# LT3045_1A_mini_module.net
KiCad netlist of a schematic drawn in EAGLE
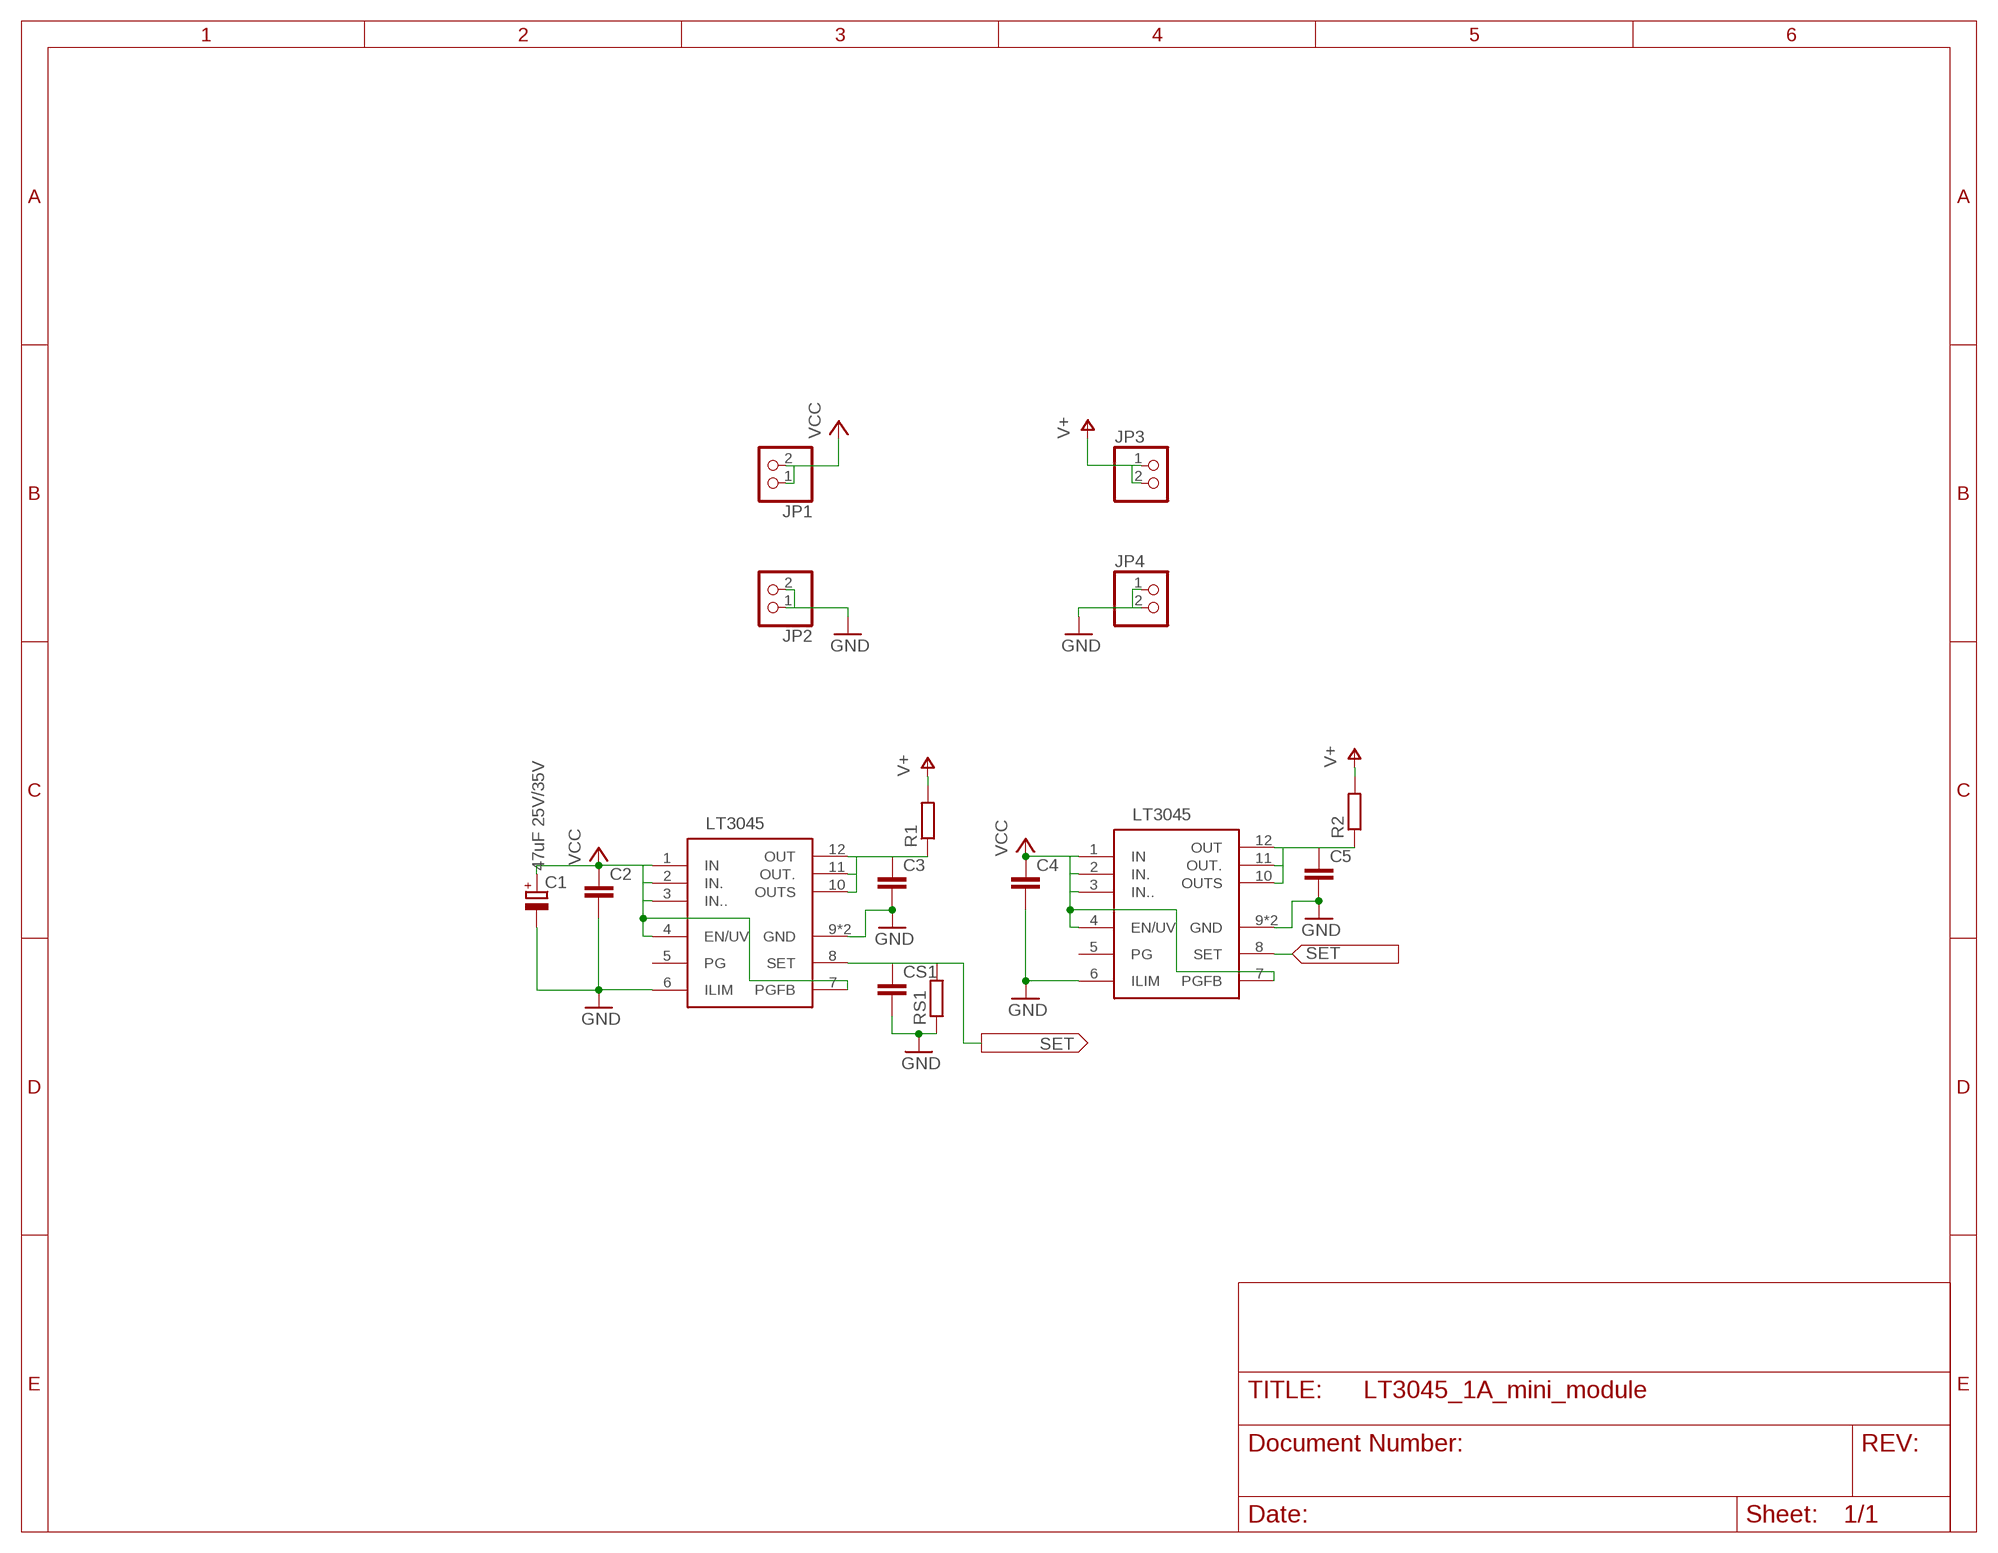
[diagram p0: schematic, sheet 1]

(export (version "E")
  (design (tool "Eeschema 10.0.6"))
  (components
    (comp (ref "C1")
      (value "47uF 25V/35V")
      (footprint "eagle-import:D_7343-31R")
      (libsource (lib "eagle-import") (part "CPOL-EUD/7343-31R"))
    )
    (comp (ref "C2")
      (value "C-EUC1206")
      (footprint "eagle-import:C1206")
      (libsource (lib "eagle-import") (part "C-EUC1206"))
    )
    (comp (ref "C3")
      (value "C-EUC1206")
      (footprint "eagle-import:C1206")
      (libsource (lib "eagle-import") (part "C-EUC1206"))
    )
    (comp (ref "C4")
      (value "C-EUC1206")
      (footprint "eagle-import:C1206")
      (libsource (lib "eagle-import") (part "C-EUC1206"))
    )
    (comp (ref "C5")
      (value "C-EUC1206")
      (footprint "eagle-import:C1206")
      (libsource (lib "eagle-import") (part "C-EUC1206"))
    )
    (comp (ref "CS1")
      (value "C-EUC0805")
      (footprint "eagle-import:C0805")
      (libsource (lib "eagle-import") (part "C-EUC0805"))
    )
    (comp (ref "JP1")
      (value "PINHD-1X2")
      (footprint "eagle-import:1X02")
      (libsource (lib "eagle-import") (part "PINHD-1X2"))
    )
    (comp (ref "JP2")
      (value "PINHD-1X2")
      (footprint "eagle-import:1X02")
      (libsource (lib "eagle-import") (part "PINHD-1X2"))
    )
    (comp (ref "JP3")
      (value "PINHD-1X2")
      (footprint "eagle-import:1X02")
      (libsource (lib "eagle-import") (part "PINHD-1X2"))
    )
    (comp (ref "JP4")
      (value "PINHD-1X2")
      (footprint "eagle-import:1X02")
      (libsource (lib "eagle-import") (part "PINHD-1X2"))
    )
    (comp (ref "R1")
      (value "R-EU_R0805")
      (footprint "eagle-import:R0805")
      (libsource (lib "eagle-import") (part "R-EU_R0805"))
    )
    (comp (ref "R2")
      (value "R-EU_R0805")
      (footprint "eagle-import:R0805")
      (libsource (lib "eagle-import") (part "R-EU_R0805"))
    )
    (comp (ref "RS1")
      (value "R-EU_R0805")
      (footprint "eagle-import:R0805")
      (libsource (lib "eagle-import") (part "R-EU_R0805"))
    )
    (comp (ref "U1")
      (value "LT3045")
      (footprint "eagle-import:MSOP12")
      (libsource (lib "eagle-import") (part "LT3045"))
    )
    (comp (ref "U2")
      (value "LT3045")
      (footprint "eagle-import:MSOP12")
      (libsource (lib "eagle-import") (part "LT3045"))
    )
  )
  (nets
    (net (code "1") (name "/SET1") (class "Default")
      (node (ref "CS1") (pin "1") (pinfunction "1_1") (pintype "passive"))
      (node (ref "RS1") (pin "2") (pinfunction "2_2") (pintype "passive"))
      (node (ref "U1") (pin "8") (pinfunction "SET_8") (pintype "bidirectional"))
      (node (ref "U2") (pin "8") (pinfunction "SET_8") (pintype "bidirectional"))
    )
    (net (code "2") (name "GND") (class "Default")
      (node (ref "C1") (pin "-") (pinfunction "-_-") (pintype "passive"))
      (node (ref "C2") (pin "2") (pinfunction "2_2") (pintype "passive"))
      (node (ref "C3") (pin "2") (pinfunction "2_2") (pintype "passive"))
      (node (ref "C4") (pin "2") (pinfunction "2_2") (pintype "passive"))
      (node (ref "C5") (pin "2") (pinfunction "2_2") (pintype "passive"))
      (node (ref "CS1") (pin "2") (pinfunction "2_2") (pintype "passive"))
      (node (ref "JP2") (pin "1") (pinfunction "1_1") (pintype "passive"))
      (node (ref "JP2") (pin "2") (pinfunction "2_2") (pintype "passive"))
      (node (ref "JP4") (pin "1") (pinfunction "1_1") (pintype "passive"))
      (node (ref "JP4") (pin "2") (pinfunction "2_2") (pintype "passive"))
      (node (ref "RS1") (pin "1") (pinfunction "1_1") (pintype "passive"))
      (node (ref "U1") (pin "6") (pinfunction "ILIM_6") (pintype "bidirectional"))
      (node (ref "U1") (pin "9") (pinfunction "GND_9") (pintype "bidirectional"))
      (node (ref "U1") (pin "EXP") (pinfunction "GND_EXP") (pintype "bidirectional"))
      (node (ref "U2") (pin "6") (pinfunction "ILIM_6") (pintype "bidirectional"))
      (node (ref "U2") (pin "9") (pinfunction "GND_9") (pintype "bidirectional"))
      (node (ref "U2") (pin "EXP") (pinfunction "GND_EXP") (pintype "bidirectional"))
    )
    (net (code "3") (name "Net-(U1-OUT)") (class "Default")
      (node (ref "C3") (pin "1") (pinfunction "1_1") (pintype "passive"))
      (node (ref "R1") (pin "1") (pinfunction "1_1") (pintype "passive"))
      (node (ref "U1") (pin "10") (pinfunction "OUTS_10") (pintype "bidirectional"))
      (node (ref "U1") (pin "11") (pinfunction "OUT._11") (pintype "bidirectional"))
      (node (ref "U1") (pin "12") (pinfunction "OUT_12") (pintype "bidirectional"))
    )
    (net (code "4") (name "Net-(U2-OUT)") (class "Default")
      (node (ref "C5") (pin "1") (pinfunction "1_1") (pintype "passive"))
      (node (ref "R2") (pin "1") (pinfunction "1_1") (pintype "passive"))
      (node (ref "U2") (pin "10") (pinfunction "OUTS_10") (pintype "bidirectional"))
      (node (ref "U2") (pin "11") (pinfunction "OUT._11") (pintype "bidirectional"))
      (node (ref "U2") (pin "12") (pinfunction "OUT_12") (pintype "bidirectional"))
    )
    (net (code "5") (name "V+") (class "Default")
      (node (ref "JP3") (pin "1") (pinfunction "1_1") (pintype "passive"))
      (node (ref "JP3") (pin "2") (pinfunction "2_2") (pintype "passive"))
      (node (ref "R1") (pin "2") (pinfunction "2_2") (pintype "passive"))
      (node (ref "R2") (pin "2") (pinfunction "2_2") (pintype "passive"))
    )
    (net (code "6") (name "VCC") (class "Default")
      (node (ref "C1") (pin "+") (pinfunction "+_+") (pintype "passive"))
      (node (ref "C2") (pin "1") (pinfunction "1_1") (pintype "passive"))
      (node (ref "C4") (pin "1") (pinfunction "1_1") (pintype "passive"))
      (node (ref "JP1") (pin "1") (pinfunction "1_1") (pintype "passive"))
      (node (ref "JP1") (pin "2") (pinfunction "2_2") (pintype "passive"))
      (node (ref "U1") (pin "1") (pinfunction "IN_1") (pintype "bidirectional"))
      (node (ref "U1") (pin "2") (pinfunction "IN._2") (pintype "bidirectional"))
      (node (ref "U1") (pin "3") (pinfunction "IN.._3") (pintype "bidirectional"))
      (node (ref "U1") (pin "4") (pinfunction "EN/UV_4") (pintype "bidirectional"))
      (node (ref "U1") (pin "7") (pinfunction "PGFB_7") (pintype "bidirectional"))
      (node (ref "U2") (pin "1") (pinfunction "IN_1") (pintype "bidirectional"))
      (node (ref "U2") (pin "2") (pinfunction "IN._2") (pintype "bidirectional"))
      (node (ref "U2") (pin "3") (pinfunction "IN.._3") (pintype "bidirectional"))
      (node (ref "U2") (pin "4") (pinfunction "EN/UV_4") (pintype "bidirectional"))
      (node (ref "U2") (pin "7") (pinfunction "PGFB_7") (pintype "bidirectional"))
    )
    (net (code "7") (name "unconnected-(U1-PG-Pad5)") (class "Default")
      (node (ref "U1") (pin "5") (pinfunction "PG_5") (pintype "bidirectional"))
    )
    (net (code "8") (name "unconnected-(U2-PG-Pad5)") (class "Default")
      (node (ref "U2") (pin "5") (pinfunction "PG_5") (pintype "bidirectional"))
    )
  )
)
